# MCU.net
KiCad netlist of a schematic drawn in Altium Designer
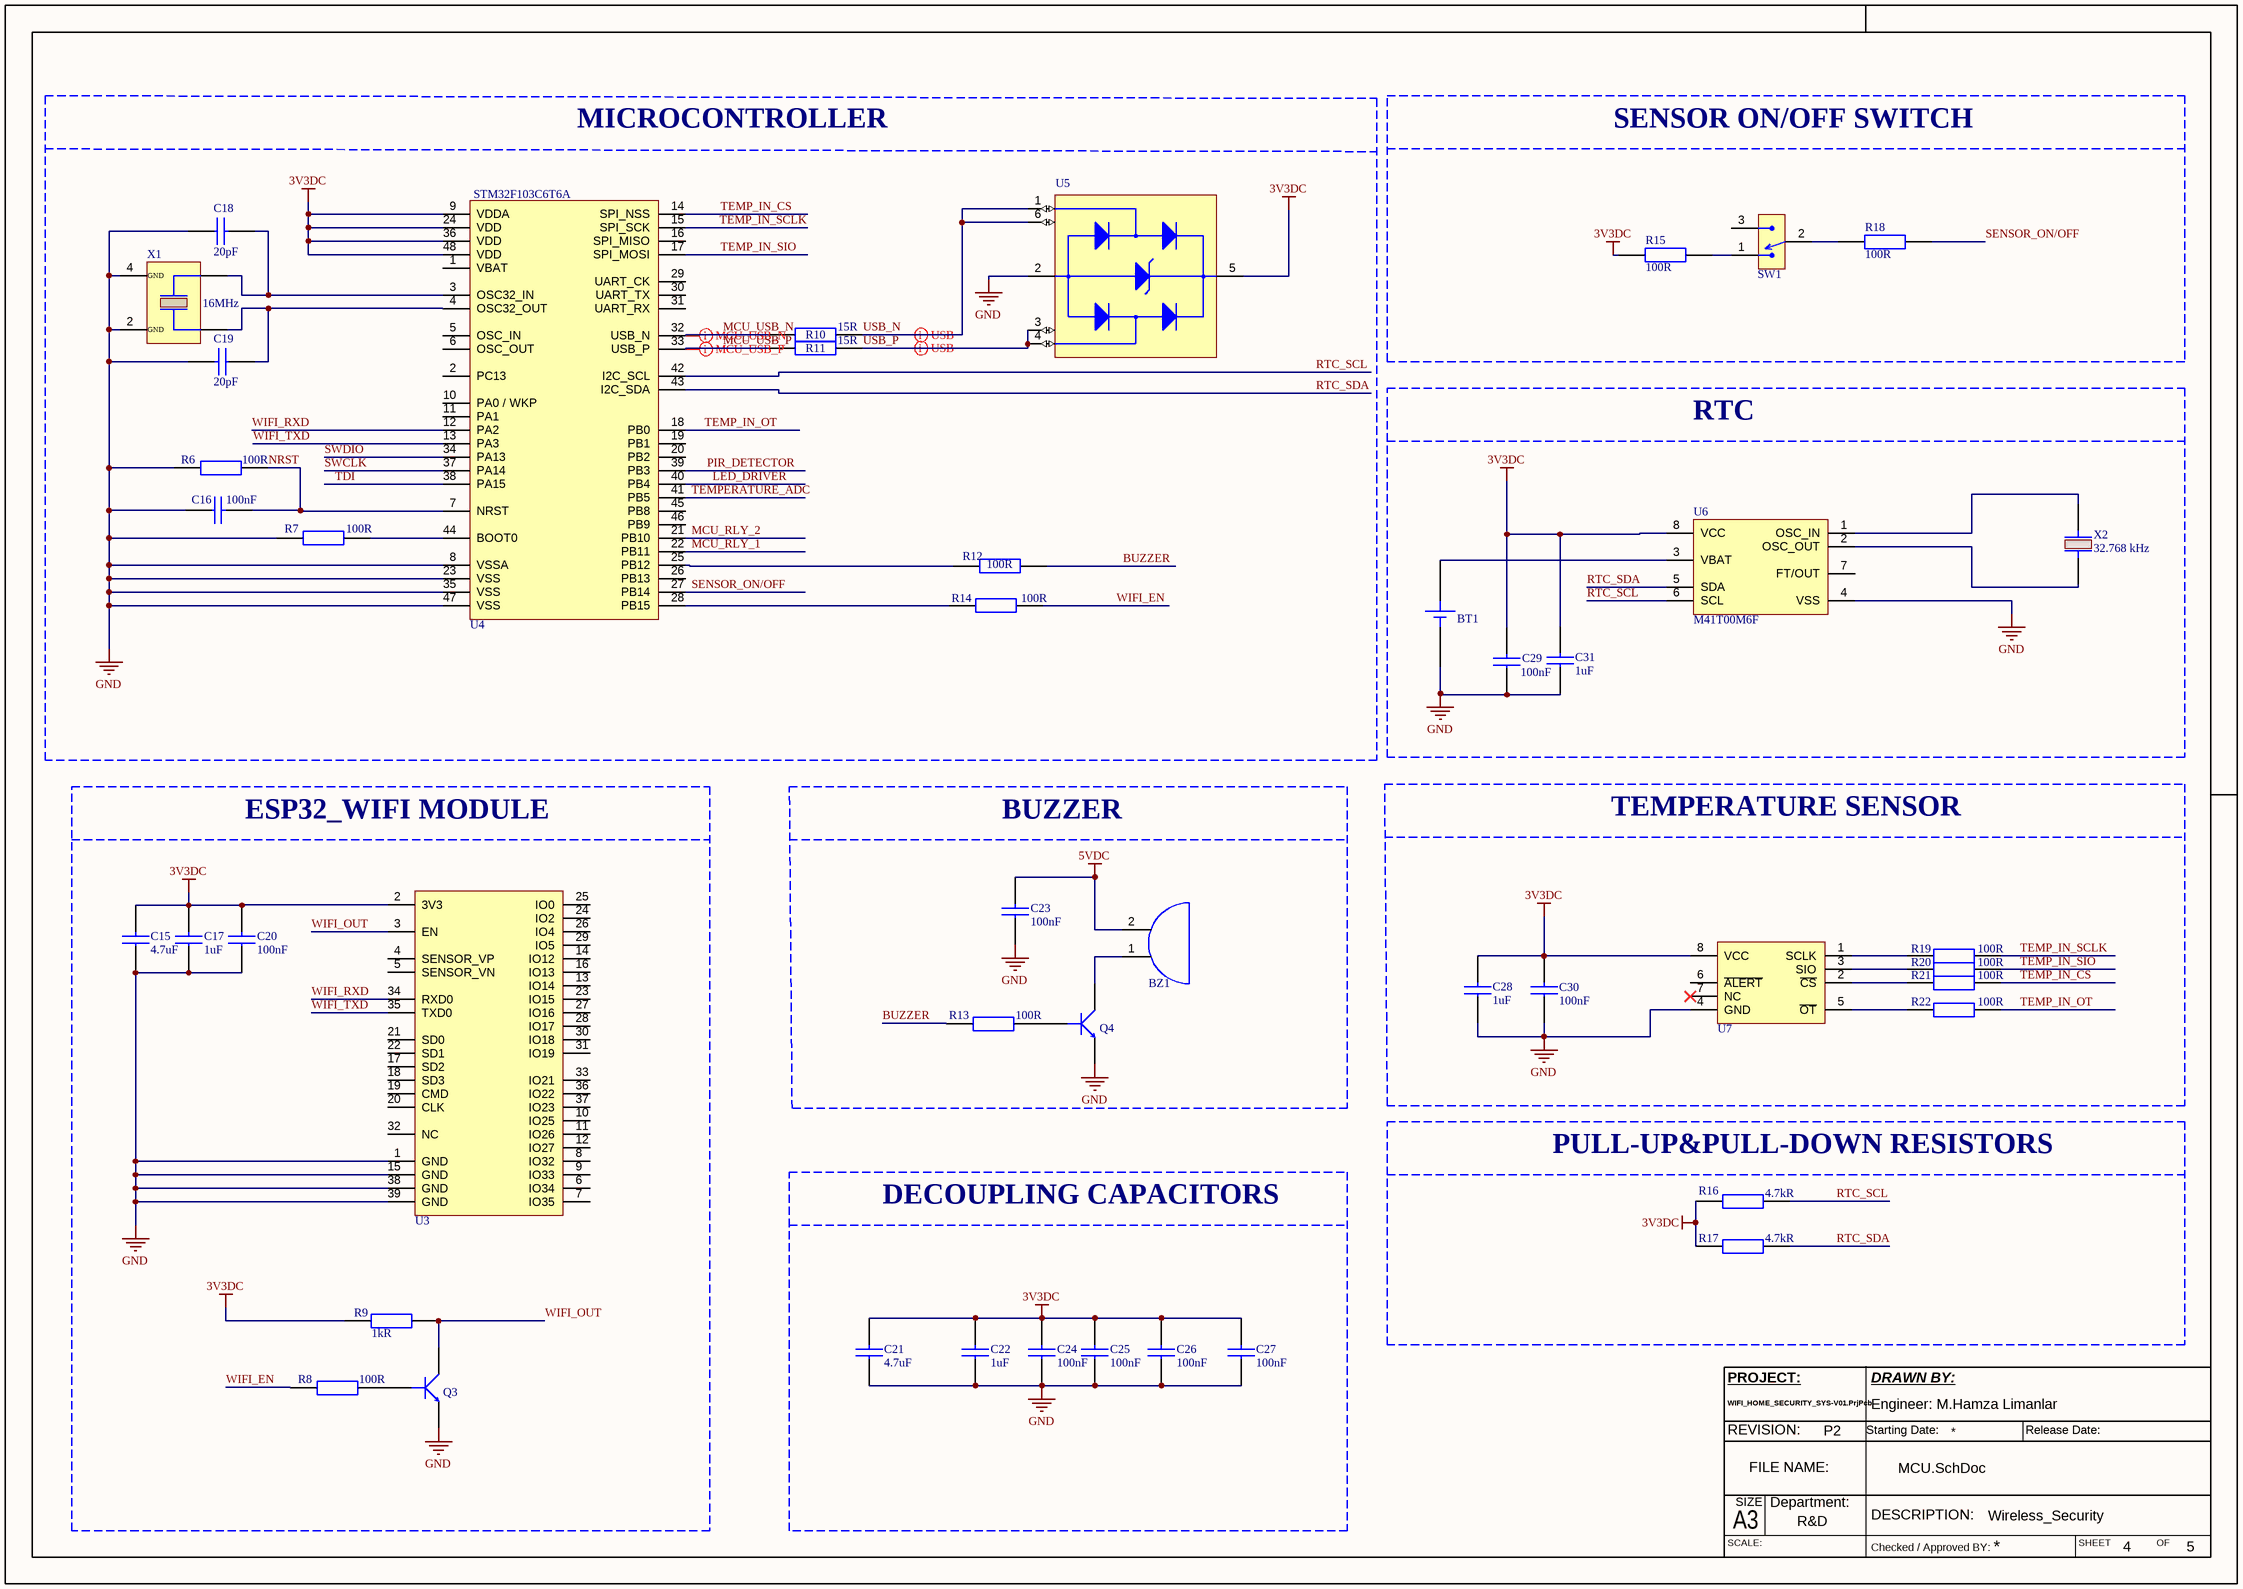
[diagram p0: MCU.SchDoc]

(export (version "E")
  (design (tool "Eeschema 10.0.6"))
  (components
    (comp (ref "BT1")
      (value "FOR CR1220")
      (footprint "1056")
      (description "BATT HOLDER COIN 12.5MM 1CEL SMD")
      (fields
        (field (name "MANUFACTURER") "Adam Equipment")
        (field (name "MANUFACTURER PART NUMBER") "BH-44A-5")
      )
      (libsource (lib "HOME_SECURITY_SYSTEM_PROJECT_SCH_LIBRARY") (part "1056"))
    )
    (comp (ref "BZ1")
      (value "CMI-9605IC-0580T")
      (footprint "CMI-9605IC")
      (description "Buzzers Indicator, Internally Driven Magnetic 5V 30mA 2.7kHz 80dB @ 5V, 10cm Through Hole PC Pins")
      (fields (field (name "MANUFACTURER") "CUI Devices") (field (name "DESIGNED BY") "M.HamzaLimanlar"))
      (libsource (lib "HOME_SECURITY_SYSTEM_PROJECT_LIB") (part "CMI-9605IC-0580T"))
    )
    (comp (ref "C15")
      (value "CL21A475KAQNNNE")
      (footprint "CAP_0805")
      (description "CAP CER 4.7uF %10 0805")
      (fields
        (field (name "MANUFACTURER") "Samsung")
        (field (name "TOLERANCE") "10%")
        (field (name "CAPACITANCE") "4.7uF")
        (field (name "DESIGNED BY") "M.HamzaLimanlar")
      )
      (libsource (lib "HOME_SECURITY_SYSTEM_PROJECT_LIB") (part "CAP CER 4.7uF 0805"))
    )
    (comp (ref "C16")
      (value "C0603C104K5RACTU")
      (footprint "CAP_0603")
      (description "CAP CER 100nF %10 0603 SMD")
      (fields
        (field (name "MANUFACTURER") "KEMET")
        (field (name "TOLERANCE") "10%")
        (field (name "CAPACITANCE") "100nF")
        (field (name "DESIGNED BY") "M.HamzaLimanlar")
      )
      (libsource (lib "HOME_SECURITY_SYSTEM_PROJECT_LIB") (part "CAP CER 100nF 0603"))
    )
    (comp (ref "C17")
      (value "CL21B105KBFNNNE")
      (footprint "CAP_0805")
      (description "CAP CER 1uF %10 0805")
      (fields
        (field (name "MANUFACTURER") "Samsung")
        (field (name "TOLERANCE") "10%")
        (field (name "CAPACITANCE") "1uF")
        (field (name "DESIGNED BY") "M.HamzaLimanlar")
      )
      (libsource (lib "HOME_SECURITY_SYSTEM_PROJECT_LIB") (part "CAP CER 1uF 0805"))
    )
    (comp (ref "C18")
      (value "CL10C200JB8NNNC")
      (footprint "CAP_0603")
      (description "CAP CER 20pF %5 0603 SMD")
      (fields
        (field (name "MANUFACTURER") "Samsung")
        (field (name "TOLERANCE") "5%")
        (field (name "CAPACITANCE") "20pF")
        (field (name "DESIGNED BY") "M.HamzaLimanlar")
      )
      (libsource (lib "HOME_SECURITY_SYSTEM_PROJECT_LIB") (part "CAP CER 20pF 0603"))
    )
    (comp (ref "C19")
      (value "CL10C200JB8NNNC")
      (footprint "CAP_0603")
      (description "CAP CER 20pF %5 0603 SMD")
      (fields
        (field (name "MANUFACTURER") "Samsung")
        (field (name "TOLERANCE") "5%")
        (field (name "CAPACITANCE") "20pF")
        (field (name "DESIGNED BY") "M.HamzaLimanlar")
      )
      (libsource (lib "HOME_SECURITY_SYSTEM_PROJECT_LIB") (part "CAP CER 20pF 0603"))
    )
    (comp (ref "C20")
      (value "CL21B104KBCNNNC")
      (footprint "CAP_0805")
      (description "CAP CER 100nF %10 0805")
      (fields
        (field (name "MANUFACTURER") "Samsung")
        (field (name "TOLERANCE") "10%")
        (field (name "CAPACITANCE") "100nF")
        (field (name "DESIGNED BY") "M.HamzaLimanlar")
      )
      (libsource (lib "HOME_SECURITY_SYSTEM_PROJECT_LIB") (part "CAP CER 100nF 0805"))
    )
    (comp (ref "C21")
      (value "CL21A475KAQNNNE")
      (footprint "CAP_0805")
      (description "CAP CER 4.7uF %10 0805")
      (fields
        (field (name "MANUFACTURER") "Samsung")
        (field (name "TOLERANCE") "10%")
        (field (name "CAPACITANCE") "4.7uF")
        (field (name "DESIGNED BY") "M.HamzaLimanlar")
      )
      (libsource (lib "HOME_SECURITY_SYSTEM_PROJECT_LIB") (part "CAP CER 4.7uF 0805"))
    )
    (comp (ref "C22")
      (value "CL21B105KBFNNNE")
      (footprint "CAP_0805")
      (description "CAP CER 1uF %10 0805")
      (fields
        (field (name "MANUFACTURER") "Samsung")
        (field (name "TOLERANCE") "10%")
        (field (name "CAPACITANCE") "1uF")
        (field (name "DESIGNED BY") "M.HamzaLimanlar")
      )
      (libsource (lib "HOME_SECURITY_SYSTEM_PROJECT_LIB") (part "CAP CER 1uF 0805"))
    )
    (comp (ref "C23")
      (value "CL21B104KBCNNNC")
      (footprint "CAP_0805")
      (description "CAP CER 100nF %10 0805")
      (fields
        (field (name "MANUFACTURER") "Samsung")
        (field (name "TOLERANCE") "10%")
        (field (name "CAPACITANCE") "100nF")
        (field (name "DESIGNED BY") "M.HamzaLimanlar")
      )
      (libsource (lib "HOME_SECURITY_SYSTEM_PROJECT_LIB") (part "CAP CER 100nF 0805"))
    )
    (comp (ref "C24")
      (value "C0603C104K5RACTU")
      (footprint "CAP_0603")
      (description "CAP CER 100nF %10 0603 SMD")
      (fields
        (field (name "MANUFACTURER") "KEMET")
        (field (name "TOLERANCE") "10%")
        (field (name "CAPACITANCE") "100nF")
        (field (name "DESIGNED BY") "M.HamzaLimanlar")
      )
      (libsource (lib "HOME_SECURITY_SYSTEM_PROJECT_LIB") (part "CAP CER 100nF 0603"))
    )
    (comp (ref "C25")
      (value "C0603C104K5RACTU")
      (footprint "CAP_0603")
      (description "CAP CER 100nF %10 0603 SMD")
      (fields
        (field (name "MANUFACTURER") "KEMET")
        (field (name "TOLERANCE") "10%")
        (field (name "CAPACITANCE") "100nF")
        (field (name "DESIGNED BY") "M.HamzaLimanlar")
      )
      (libsource (lib "HOME_SECURITY_SYSTEM_PROJECT_LIB") (part "CAP CER 100nF 0603"))
    )
    (comp (ref "C26")
      (value "C0603C104K5RACTU")
      (footprint "CAP_0603")
      (description "CAP CER 100nF %10 0603 SMD")
      (fields
        (field (name "MANUFACTURER") "KEMET")
        (field (name "TOLERANCE") "10%")
        (field (name "CAPACITANCE") "100nF")
        (field (name "DESIGNED BY") "M.HamzaLimanlar")
      )
      (libsource (lib "HOME_SECURITY_SYSTEM_PROJECT_LIB") (part "CAP CER 100nF 0603"))
    )
    (comp (ref "C27")
      (value "C0603C104K5RACTU")
      (footprint "CAP_0603")
      (description "CAP CER 100nF %10 0603 SMD")
      (fields
        (field (name "MANUFACTURER") "KEMET")
        (field (name "TOLERANCE") "10%")
        (field (name "CAPACITANCE") "100nF")
        (field (name "DESIGNED BY") "M.HamzaLimanlar")
      )
      (libsource (lib "HOME_SECURITY_SYSTEM_PROJECT_LIB") (part "CAP CER 100nF 0603"))
    )
    (comp (ref "C28")
      (value "CL21B105KBFNNNE")
      (footprint "CAP_0805")
      (description "CAP CER 1uF %10 0805")
      (fields
        (field (name "MANUFACTURER") "Samsung")
        (field (name "TOLERANCE") "10%")
        (field (name "CAPACITANCE") "1uF")
        (field (name "DESIGNED BY") "M.HamzaLimanlar")
      )
      (libsource (lib "HOME_SECURITY_SYSTEM_PROJECT_LIB") (part "CAP CER 1uF 0805"))
    )
    (comp (ref "C29")
      (value "CL21B104KBCNNNC")
      (footprint "CAP_0805")
      (description "CAP CER 100nF %10 0805")
      (fields
        (field (name "MANUFACTURER") "Samsung")
        (field (name "TOLERANCE") "10%")
        (field (name "CAPACITANCE") "100nF")
        (field (name "DESIGNED BY") "M.HamzaLimanlar")
      )
      (libsource (lib "HOME_SECURITY_SYSTEM_PROJECT_LIB") (part "CAP CER 100nF 0805"))
    )
    (comp (ref "C30")
      (value "CL21B104KBCNNNC")
      (footprint "CAP_0805")
      (description "CAP CER 100nF %10 0805")
      (fields
        (field (name "MANUFACTURER") "Samsung")
        (field (name "TOLERANCE") "10%")
        (field (name "CAPACITANCE") "100nF")
        (field (name "DESIGNED BY") "M.HamzaLimanlar")
      )
      (libsource (lib "HOME_SECURITY_SYSTEM_PROJECT_LIB") (part "CAP CER 100nF 0805"))
    )
    (comp (ref "C31")
      (value "CL21B105KBFNNNE")
      (footprint "CAP_0805")
      (description "CAP CER 1uF %10 0805")
      (fields
        (field (name "MANUFACTURER") "Samsung")
        (field (name "TOLERANCE") "10%")
        (field (name "CAPACITANCE") "1uF")
        (field (name "DESIGNED BY") "M.HamzaLimanlar")
      )
      (libsource (lib "HOME_SECURITY_SYSTEM_PROJECT_LIB") (part "CAP CER 1uF 0805"))
    )
    (comp (ref "Q3")
      (value "MMBT3904-7-F")
      (footprint "SOT-23F")
      (description "Transistor General Purpose BJT NPN 40 Volt 0.2A Automotive 3-Pin SOT-23")
      (fields (field (name "MANUFACTURER") "Diodes Zetex") (field (name "DESIGNED BY") "M.HamzaLimanlar"))
      (libsource (lib "HOME_SECURITY_SYSTEM_PROJECT_LIB") (part "MMBT3904-7-F"))
    )
    (comp (ref "Q4")
      (value "MMBT3904-7-F")
      (footprint "SOT-23F")
      (description "Transistor General Purpose BJT NPN 40 Volt 0.2A Automotive 3-Pin SOT-23")
      (fields (field (name "MANUFACTURER") "Diodes Zetex") (field (name "DESIGNED BY") "M.HamzaLimanlar"))
      (libsource (lib "HOME_SECURITY_SYSTEM_PROJECT_LIB") (part "MMBT3904-7-F"))
    )
    (comp (ref "R6")
      (value "RC0603JR-07100RL")
      (footprint "RES_0603")
      (description "RES 100 %5 OHM 0603 SMD")
      (fields
        (field (name "MANUFACTURER") "Yageo")
        (field (name "TOLERANCE") "5%")
        (field (name "RESISTANCE") "100R")
        (field (name "DESIGNED BY") "M.HamzaLimanlar")
      )
      (libsource (lib "HOME_SECURITY_SYSTEM_PROJECT_LIB") (part "RES 100 OHM 0603"))
    )
    (comp (ref "R7")
      (value "RC0603JR-07100RL")
      (footprint "RES_0603")
      (description "RES 100 %5 OHM 0603 SMD")
      (fields
        (field (name "MANUFACTURER") "Yageo")
        (field (name "TOLERANCE") "5%")
        (field (name "RESISTANCE") "100R")
        (field (name "DESIGNED BY") "M.HamzaLimanlar")
      )
      (libsource (lib "HOME_SECURITY_SYSTEM_PROJECT_LIB") (part "RES 100 OHM 0603"))
    )
    (comp (ref "R8")
      (value "RC0603JR-07100RL")
      (footprint "RES_0603")
      (description "RES 100 %5 OHM 0603 SMD")
      (fields
        (field (name "MANUFACTURER") "Yageo")
        (field (name "TOLERANCE") "5%")
        (field (name "RESISTANCE") "100R")
        (field (name "DESIGNED BY") "M.HamzaLimanlar")
      )
      (libsource (lib "HOME_SECURITY_SYSTEM_PROJECT_LIB") (part "RES 100 OHM 0603"))
    )
    (comp (ref "R9")
      (value "RC0603FR-0710KL")
      (footprint "RES_0603")
      (description "RES 1K %1 OHM 0603 SMD")
      (fields
        (field (name "MANUFACTURER") "Yageo")
        (field (name "MANUFACTURER PART NUMBER") "RC0603JR-071KL")
        (field (name "RESISTANCE") "1kR")
        (field (name "DESIGNED BY") "M.HamzaLimanlar")
      )
      (libsource (lib "HOME_SECURITY_SYSTEM_PROJECT_LIB") (part "RES 1K OHM 0603"))
    )
    (comp (ref "R10")
      (value "RC0603JR-0715RL")
      (footprint "RES_0603")
      (description "RES 15 %5 OHM 0603 SMD")
      (fields
        (field (name "MANUFACTURER") "Yageo")
        (field (name "TOLERANCE") "5%")
        (field (name "RESISTANCE") "15R")
        (field (name "DESIGNED BY") "M.HamzaLimanlar")
      )
      (libsource (lib "HOME_SECURITY_SYSTEM_PROJECT_LIB") (part "RES 15 OHM 0603"))
    )
    (comp (ref "R11")
      (value "RC0603JR-0715RL")
      (footprint "RES_0603")
      (description "RES 15 %5 OHM 0603 SMD")
      (fields
        (field (name "MANUFACTURER") "Yageo")
        (field (name "TOLERANCE") "5%")
        (field (name "RESISTANCE") "15R")
        (field (name "DESIGNED BY") "M.HamzaLimanlar")
      )
      (libsource (lib "HOME_SECURITY_SYSTEM_PROJECT_LIB") (part "RES 15 OHM 0603"))
    )
    (comp (ref "R12")
      (value "RC0603JR-07100RL")
      (footprint "RES_0603")
      (description "RES 100 %5 OHM 0603 SMD")
      (fields
        (field (name "MANUFACTURER") "Yageo")
        (field (name "TOLERANCE") "5%")
        (field (name "RESISTANCE") "100R")
        (field (name "DESIGNED BY") "M.HamzaLimanlar")
      )
      (libsource (lib "HOME_SECURITY_SYSTEM_PROJECT_LIB") (part "RES 100 OHM 0603"))
    )
    (comp (ref "R13")
      (value "RC0603JR-07100RL")
      (footprint "RES_0603")
      (description "RES 100 %5 OHM 0603 SMD")
      (fields
        (field (name "MANUFACTURER") "Yageo")
        (field (name "TOLERANCE") "5%")
        (field (name "RESISTANCE") "100R")
        (field (name "DESIGNED BY") "M.HamzaLimanlar")
      )
      (libsource (lib "HOME_SECURITY_SYSTEM_PROJECT_LIB") (part "RES 100 OHM 0603"))
    )
    (comp (ref "R14")
      (value "RC0603JR-07100RL")
      (footprint "RES_0603")
      (description "RES 100 %5 OHM 0603 SMD")
      (fields
        (field (name "MANUFACTURER") "Yageo")
        (field (name "TOLERANCE") "5%")
        (field (name "RESISTANCE") "100R")
        (field (name "DESIGNED BY") "M.HamzaLimanlar")
      )
      (libsource (lib "HOME_SECURITY_SYSTEM_PROJECT_LIB") (part "RES 100 OHM 0603"))
    )
    (comp (ref "R15")
      (value "RC0603JR-07100RL")
      (footprint "RES_0603")
      (description "RES 100 %5 OHM 0603 SMD")
      (fields
        (field (name "MANUFACTURER") "Yageo")
        (field (name "TOLERANCE") "5%")
        (field (name "RESISTANCE") "100R")
        (field (name "DESIGNED BY") "M.HamzaLimanlar")
      )
      (libsource (lib "HOME_SECURITY_SYSTEM_PROJECT_LIB") (part "RES 100 OHM 0603"))
    )
    (comp (ref "R16")
      (value "RC0603JR-074K7L")
      (footprint "RES_0603")
      (description "RES 4K7 %5 OHM 0603 SMD")
      (fields
        (field (name "MANUFACTURER") "Yageo")
        (field (name "TOLERANCE") "5%")
        (field (name "RESISTANCE") "4.7kR")
        (field (name "DESIGNED BY") "M.HamzaLimanlar")
      )
      (libsource (lib "HOME_SECURITY_SYSTEM_PROJECT_LIB") (part "RES 4K7 OHM 0603"))
    )
    (comp (ref "R17")
      (value "RC0603JR-074K7L")
      (footprint "RES_0603")
      (description "RES 4K7 %5 OHM 0603 SMD")
      (fields
        (field (name "MANUFACTURER") "Yageo")
        (field (name "TOLERANCE") "5%")
        (field (name "RESISTANCE") "4.7kR")
        (field (name "DESIGNED BY") "M.HamzaLimanlar")
      )
      (libsource (lib "HOME_SECURITY_SYSTEM_PROJECT_LIB") (part "RES 4K7 OHM 0603"))
    )
    (comp (ref "R18")
      (value "RC0603JR-07100RL")
      (footprint "RES_0603")
      (description "RES 100 %5 OHM 0603 SMD")
      (fields
        (field (name "MANUFACTURER") "Yageo")
        (field (name "TOLERANCE") "5%")
        (field (name "RESISTANCE") "100R")
        (field (name "DESIGNED BY") "M.HamzaLimanlar")
      )
      (libsource (lib "HOME_SECURITY_SYSTEM_PROJECT_LIB") (part "RES 100 OHM 0603"))
    )
    (comp (ref "R19")
      (value "RC0603JR-07100RL")
      (footprint "RES_0603")
      (description "RES 100 %5 OHM 0603 SMD")
      (fields
        (field (name "MANUFACTURER") "Yageo")
        (field (name "TOLERANCE") "5%")
        (field (name "RESISTANCE") "100R")
        (field (name "DESIGNED BY") "M.HamzaLimanlar")
      )
      (libsource (lib "HOME_SECURITY_SYSTEM_PROJECT_LIB") (part "RES 100 OHM 0603"))
    )
    (comp (ref "R20")
      (value "RC0603JR-07100RL")
      (footprint "RES_0603")
      (description "RES 100 %5 OHM 0603 SMD")
      (fields
        (field (name "MANUFACTURER") "Yageo")
        (field (name "TOLERANCE") "5%")
        (field (name "RESISTANCE") "100R")
        (field (name "DESIGNED BY") "M.HamzaLimanlar")
      )
      (libsource (lib "HOME_SECURITY_SYSTEM_PROJECT_LIB") (part "RES 100 OHM 0603"))
    )
    (comp (ref "R21")
      (value "RC0603JR-07100RL")
      (footprint "RES_0603")
      (description "RES 100 %5 OHM 0603 SMD")
      (fields
        (field (name "MANUFACTURER") "Yageo")
        (field (name "TOLERANCE") "5%")
        (field (name "RESISTANCE") "100R")
        (field (name "DESIGNED BY") "M.HamzaLimanlar")
      )
      (libsource (lib "HOME_SECURITY_SYSTEM_PROJECT_LIB") (part "RES 100 OHM 0603"))
    )
    (comp (ref "R22")
      (value "RC0603JR-07100RL")
      (footprint "RES_0603")
      (description "RES 100 %5 OHM 0603 SMD")
      (fields
        (field (name "MANUFACTURER") "Yageo")
        (field (name "TOLERANCE") "5%")
        (field (name "RESISTANCE") "100R")
        (field (name "DESIGNED BY") "M.HamzaLimanlar")
      )
      (libsource (lib "HOME_SECURITY_SYSTEM_PROJECT_LIB") (part "RES 100 OHM 0603"))
    )
    (comp (ref "SW1")
      (value "EG1215AA")
      (footprint "EG1215AA")
      (description "Slide Switch, SPDT, 0.025A, 24V, SMD")
      (fields
        (field (name "MANUFACTURER") "E-Switch")
        (field (name "TOLERANCE") "4.95%")
        (field (name "DESIGNED BY") "M.HamzaLimanlar")
      )
      (libsource (lib "HOME_SECURITY_SYSTEM_PROJECT_LIB") (part "EG1215AA"))
    )
    (comp (ref "U3")
      (value "ESP32-WROOM-32")
      (footprint "ESP32-32")
      (description "SMD MODULE, ESP32-D0WDQ6, 32MBIT")
      (fields
        (field (name "MANUFACTURER") "Espressif Systems")
        (field (name "DESIGNED BY") "M.HamzaLimanlar")
      )
      (libsource (lib "HOME_SECURITY_SYSTEM_PROJECT_LIB") (part "ESP32-WROOM-32"))
    )
    (comp (ref "U4")
      (value "STM32F103C6T6A")
      (footprint "LQFP-48")
      (description "MCU 32-bit STM32F ARM Cortex M3 RISC 32KB Flash 2.5V/3.3V 48-Pin LQFP Tray")
      (fields
        (field (name "MANUFACTURER") "STMicroelectronics")
        (field (name "DESIGNED BY") "M.HamzaLimanlar")
      )
      (libsource (lib "HOME_SECURITY_SYSTEM_PROJECT_LIB") (part "STM32F103C6T6A"))
    )
    (comp (ref "U5")
      (value "USBLC6-2SC6")
      (footprint "SOT23-6L")
      (description "TVS DIODE 5.25V 17V SOT23-6")
      (fields
        (field (name "MANUFACTURER") "STMicroelectronics")
        (field (name "DESIGNED BY") "M.HamzaLimanlar")
      )
      (libsource (lib "HOME_SECURITY_SYSTEM_PROJECT_LIB") (part "USB PROTECTION"))
    )
    (comp (ref "U6")
      (value "M41T00M6F")
      (footprint "SOIC8")
      (description "IC RTC CLK/CALENDAR I2C 8-SOIC")
      (fields
        (field (name "MANUFACTURER") "STMicroelectronics")
        (field (name "MANUFACTURER PART NUMBER") "M41T00M6F")
        (field (name "DESIGNED BY") "M.HamzaLimanlar")
      )
      (libsource (lib "HOME_SECURITY_SYSTEM_PROJECT_LIB") (part "M41T00M6F"))
    )
    (comp (ref "U7")
      (value "MAX6662")
      (footprint "SOIC8")
      (description "SENSOR TEMPERATURE SPI 8SOIC")
      (fields
        (field (name "MANUFACTURER") "Maxim")
        (field (name "MANUFACTURER PART NUMBER") "MAX6662MSA+")
        (field (name "DESIGNED BY") "M.HamzaLimanlar")
      )
      (libsource (lib "HOME_SECURITY_SYSTEM_PROJECT_LIB") (part "MAX6662"))
    )
    (comp (ref "X1")
      (value "ECS-160-20-30B-TR")
      (footprint "ECS")
      (description "CRYSTAL 16.0000MHZ 20PF SMD")
      (fields
        (field (name "MANUFACTURER") "ECS International")
        (field (name "TOLERANCE") "50ppm")
        (field (name "FREQUENCY") "16MHz")
        (field (name "DESIGNED BY") "M.HamzaLimanlar")
      )
      (libsource (lib "HOME_SECURITY_SYSTEM_PROJECT_LIB") (part "CRYSTAL 16MHz"))
    )
    (comp (ref "X2")
      (value "ABS05-32.768KHZ-T")
      (footprint "ABS05")
      (description "Crystal, 32.768 kHz, SMD, 1.6mm x 1mm, 12.5 pF, 20 ppm, ABS05 Series")
      (fields
        (field (name "MANUFACTURER") "Abracon")
        (field (name "TOLERANCE") "20ppm")
        (field (name "OPERATING FREQUENCY") "32.768 kHz")
        (field (name "DESIGNED BY") "M.HamzaLimanlar")
      )
      (libsource (lib "HOME_SECURITY_SYSTEM_PROJECT_LIB") (part "CRYSTAL 32768kHZ"))
    )
  )
  (nets
    (net (code "1") (name "/BUZZER") (class "Default")
      (node (ref "R12") (pin "2") (pinfunction "2_2") (pintype "passive"))
      (node (ref "R13") (pin "1") (pinfunction "1_1") (pintype "passive"))
    )
    (net (code "2") (name "/LED_DRIVER") (class "Default")
      (node (ref "U4") (pin "40") (pinfunction "PB4_40") (pintype "passive"))
    )
    (net (code "3") (name "/MCU_RLY_1") (class "Default")
      (node (ref "U4") (pin "22") (pinfunction "PB11_22") (pintype "passive"))
    )
    (net (code "4") (name "/MCU_RLY_2") (class "Default")
      (node (ref "U4") (pin "21") (pinfunction "PB10_21") (pintype "passive"))
    )
    (net (code "5") (name "/MCU_USB_N") (class "Default")
      (node (ref "R10") (pin "1") (pinfunction "1_1") (pintype "passive"))
      (node (ref "U4") (pin "32") (pinfunction "USB_N_32") (pintype "passive"))
    )
    (net (code "6") (name "/MCU_USB_P") (class "Default")
      (node (ref "R11") (pin "1") (pinfunction "1_1") (pintype "passive"))
      (node (ref "U4") (pin "33") (pinfunction "USB_P_33") (pintype "passive"))
    )
    (net (code "7") (name "/NRST") (class "Default")
      (node (ref "C16") (pin "2") (pinfunction "2_2") (pintype "passive"))
      (node (ref "R6") (pin "2") (pinfunction "2_2") (pintype "passive"))
      (node (ref "U4") (pin "7") (pinfunction "NRST_7") (pintype "passive"))
    )
    (net (code "8") (name "/PIR_DETECTOR") (class "Default")
      (node (ref "U4") (pin "39") (pinfunction "PB3_39") (pintype "passive"))
    )
    (net (code "9") (name "/RTC_SCL") (class "Default")
      (node (ref "R16") (pin "2") (pinfunction "2_2") (pintype "passive"))
      (node (ref "U4") (pin "42") (pinfunction "I2C_SCL_42") (pintype "passive"))
      (node (ref "U6") (pin "6") (pinfunction "SCL_6") (pintype "passive"))
    )
    (net (code "10") (name "/RTC_SDA") (class "Default")
      (node (ref "R17") (pin "2") (pinfunction "2_2") (pintype "passive"))
      (node (ref "U4") (pin "43") (pinfunction "I2C_SDA_43") (pintype "passive"))
      (node (ref "U6") (pin "5") (pinfunction "SDA_5") (pintype "passive"))
    )
    (net (code "11") (name "/SENSOR_ON{slash}OFF") (class "Default")
      (node (ref "R18") (pin "2") (pinfunction "2_2") (pintype "passive"))
      (node (ref "U4") (pin "27") (pinfunction "PB14_27") (pintype "passive"))
    )
    (net (code "12") (name "/SWCLK") (class "Default")
      (node (ref "U4") (pin "37") (pinfunction "PA14_37") (pintype "passive"))
    )
    (net (code "13") (name "/SWDIO") (class "Default")
      (node (ref "U4") (pin "34") (pinfunction "PA13_34") (pintype "passive"))
    )
    (net (code "14") (name "/TDI") (class "Default")
      (node (ref "U4") (pin "38") (pinfunction "PA15_38") (pintype "passive"))
    )
    (net (code "15") (name "/TEMPERATURE_ADC") (class "Default")
      (node (ref "U4") (pin "41") (pinfunction "PB5_41") (pintype "passive"))
    )
    (net (code "16") (name "/TEMP_IN_CS") (class "Default")
      (node (ref "R21") (pin "2") (pinfunction "2_2") (pintype "passive"))
      (node (ref "U4") (pin "14") (pinfunction "SPI_NSS_14") (pintype "passive"))
    )
    (net (code "17") (name "/TEMP_IN_OT") (class "Default")
      (node (ref "R22") (pin "2") (pinfunction "2_2") (pintype "passive"))
      (node (ref "U4") (pin "18") (pinfunction "PB0_18") (pintype "passive"))
    )
    (net (code "18") (name "/TEMP_IN_SCLK") (class "Default")
      (node (ref "R19") (pin "2") (pinfunction "2_2") (pintype "passive"))
      (node (ref "U4") (pin "15") (pinfunction "SPI_SCK_15") (pintype "passive"))
    )
    (net (code "19") (name "/TEMP_IN_SIO") (class "Default")
      (node (ref "R20") (pin "2") (pinfunction "2_2") (pintype "passive"))
      (node (ref "U4") (pin "17") (pinfunction "SPI_MOSI_17") (pintype "passive"))
    )
    (net (code "20") (name "/USB_N") (class "Default")
      (node (ref "R10") (pin "2") (pinfunction "2_2") (pintype "passive"))
      (node (ref "U5") (pin "1") (pinfunction "I/O1_1") (pintype "bidirectional"))
      (node (ref "U5") (pin "6") (pinfunction "I/O1_6") (pintype "bidirectional"))
    )
    (net (code "21") (name "/USB_P") (class "Default")
      (node (ref "R11") (pin "2") (pinfunction "2_2") (pintype "passive"))
      (node (ref "U5") (pin "3") (pinfunction "I/O2_3") (pintype "bidirectional"))
      (node (ref "U5") (pin "4") (pinfunction "I/O2_4") (pintype "bidirectional"))
    )
    (net (code "22") (name "/WIFI_EN") (class "Default")
      (node (ref "R14") (pin "2") (pinfunction "2_2") (pintype "passive"))
      (node (ref "R8") (pin "1") (pinfunction "1_1") (pintype "passive"))
    )
    (net (code "23") (name "/WIFI_OUT") (class "Default")
      (node (ref "Q3") (pin "3") (pinfunction "C_3") (pintype "power_in"))
      (node (ref "R9") (pin "2") (pinfunction "2_2") (pintype "passive"))
      (node (ref "U3") (pin "3") (pinfunction "EN_3") (pintype "passive"))
    )
    (net (code "24") (name "/WIFI_RXD") (class "Default")
      (node (ref "U3") (pin "34") (pinfunction "RXD0_34") (pintype "passive"))
      (node (ref "U4") (pin "12") (pinfunction "PA2_12") (pintype "passive"))
    )
    (net (code "25") (name "/WIFI_TXD") (class "Default")
      (node (ref "U3") (pin "35") (pinfunction "TXD0_35") (pintype "passive"))
      (node (ref "U4") (pin "13") (pinfunction "PA3_13") (pintype "passive"))
    )
    (net (code "26") (name "3V3DC") (class "Default")
      (node (ref "C15") (pin "2") (pinfunction "2_2") (pintype "passive"))
      (node (ref "C17") (pin "2") (pinfunction "2_2") (pintype "passive"))
      (node (ref "C20") (pin "2") (pinfunction "2_2") (pintype "passive"))
      (node (ref "C21") (pin "2") (pinfunction "2_2") (pintype "passive"))
      (node (ref "C22") (pin "2") (pinfunction "2_2") (pintype "passive"))
      (node (ref "C24") (pin "2") (pinfunction "2_2") (pintype "passive"))
      (node (ref "C25") (pin "2") (pinfunction "2_2") (pintype "passive"))
      (node (ref "C26") (pin "2") (pinfunction "2_2") (pintype "passive"))
      (node (ref "C27") (pin "2") (pinfunction "2_2") (pintype "passive"))
      (node (ref "C28") (pin "2") (pinfunction "2_2") (pintype "passive"))
      (node (ref "C29") (pin "2") (pinfunction "2_2") (pintype "passive"))
      (node (ref "C30") (pin "2") (pinfunction "2_2") (pintype "passive"))
      (node (ref "C31") (pin "2") (pinfunction "2_2") (pintype "passive"))
      (node (ref "R15") (pin "1") (pinfunction "1_1") (pintype "passive"))
      (node (ref "R16") (pin "1") (pinfunction "1_1") (pintype "passive"))
      (node (ref "R17") (pin "1") (pinfunction "1_1") (pintype "passive"))
      (node (ref "R9") (pin "1") (pinfunction "1_1") (pintype "passive"))
      (node (ref "U3") (pin "2") (pinfunction "3V3_2") (pintype "passive"))
      (node (ref "U4") (pin "24") (pinfunction "VDD_24") (pintype "passive"))
      (node (ref "U4") (pin "36") (pinfunction "VDD_36") (pintype "passive"))
      (node (ref "U4") (pin "48") (pinfunction "VDD_48") (pintype "passive"))
      (node (ref "U4") (pin "9") (pinfunction "VDDA_9") (pintype "passive"))
      (node (ref "U5") (pin "5") (pinfunction "VBUS_5") (pintype "power_in"))
      (node (ref "U6") (pin "8") (pinfunction "VCC_8") (pintype "passive"))
      (node (ref "U7") (pin "8") (pinfunction "VCC_8") (pintype "passive"))
    )
    (net (code "27") (name "5VDC") (class "Default")
      (node (ref "BZ1") (pin "2") (pinfunction "2_2") (pintype "passive"))
      (node (ref "C23") (pin "2") (pinfunction "2_2") (pintype "passive"))
    )
    (net (code "28") (name "GND") (class "Default")
      (node (ref "BT1") (pin "2") (pinfunction "2_2") (pintype "passive"))
      (node (ref "C15") (pin "1") (pinfunction "1_1") (pintype "passive"))
      (node (ref "C16") (pin "1") (pinfunction "1_1") (pintype "passive"))
      (node (ref "C17") (pin "1") (pinfunction "1_1") (pintype "passive"))
      (node (ref "C18") (pin "1") (pinfunction "1_1") (pintype "passive"))
      (node (ref "C19") (pin "2") (pinfunction "2_2") (pintype "passive"))
      (node (ref "C20") (pin "1") (pinfunction "1_1") (pintype "passive"))
      (node (ref "C21") (pin "1") (pinfunction "1_1") (pintype "passive"))
      (node (ref "C22") (pin "1") (pinfunction "1_1") (pintype "passive"))
      (node (ref "C23") (pin "1") (pinfunction "1_1") (pintype "passive"))
      (node (ref "C24") (pin "1") (pinfunction "1_1") (pintype "passive"))
      (node (ref "C25") (pin "1") (pinfunction "1_1") (pintype "passive"))
      (node (ref "C26") (pin "1") (pinfunction "1_1") (pintype "passive"))
      (node (ref "C27") (pin "1") (pinfunction "1_1") (pintype "passive"))
      (node (ref "C28") (pin "1") (pinfunction "1_1") (pintype "passive"))
      (node (ref "C29") (pin "1") (pinfunction "1_1") (pintype "passive"))
      (node (ref "C30") (pin "1") (pinfunction "1_1") (pintype "passive"))
      (node (ref "C31") (pin "1") (pinfunction "1_1") (pintype "passive"))
      (node (ref "Q3") (pin "2") (pinfunction "E_2") (pintype "power_in"))
      (node (ref "Q4") (pin "2") (pinfunction "E_2") (pintype "power_in"))
      (node (ref "R6") (pin "1") (pinfunction "1_1") (pintype "passive"))
      (node (ref "R7") (pin "1") (pinfunction "1_1") (pintype "passive"))
      (node (ref "U3") (pin "1") (pinfunction "GND_1") (pintype "passive"))
      (node (ref "U3") (pin "15") (pinfunction "GND_15") (pintype "passive"))
      (node (ref "U3") (pin "38") (pinfunction "GND_38") (pintype "passive"))
      (node (ref "U3") (pin "39") (pinfunction "GND_39") (pintype "passive"))
      (node (ref "U4") (pin "23") (pinfunction "VSS_23") (pintype "passive"))
      (node (ref "U4") (pin "35") (pinfunction "VSS_35") (pintype "passive"))
      (node (ref "U4") (pin "47") (pinfunction "VSS_47") (pintype "passive"))
      (node (ref "U4") (pin "8") (pinfunction "VSSA_8") (pintype "passive"))
      (node (ref "U5") (pin "2") (pinfunction "GND_2") (pintype "power_in"))
      (node (ref "U6") (pin "4") (pinfunction "VSS_4") (pintype "passive"))
      (node (ref "U7") (pin "4") (pinfunction "GND_4") (pintype "passive"))
      (node (ref "X1") (pin "2") (pinfunction "GND_2") (pintype "passive"))
      (node (ref "X1") (pin "4") (pinfunction "GND_4") (pintype "passive"))
    )
    (net (code "29") (name "Net-(Q3-B)") (class "Default")
      (node (ref "Q3") (pin "1") (pinfunction "B_1") (pintype "power_in"))
      (node (ref "R8") (pin "2") (pinfunction "2_2") (pintype "passive"))
    )
    (net (code "30") (name "Net-(Q4-B)") (class "Default")
      (node (ref "Q4") (pin "1") (pinfunction "B_1") (pintype "power_in"))
      (node (ref "R13") (pin "2") (pinfunction "2_2") (pintype "passive"))
    )
    (net (code "31") (name "Net-(Q4-C)") (class "Default")
      (node (ref "BZ1") (pin "1") (pinfunction "1_1") (pintype "passive"))
      (node (ref "Q4") (pin "3") (pinfunction "C_3") (pintype "power_in"))
    )
    (net (code "32") (name "Net-(R15-Pad2)") (class "Default")
      (node (ref "R15") (pin "2") (pinfunction "2_2") (pintype "passive"))
      (node (ref "SW1") (pin "1") (pinfunction "1_1") (pintype "passive"))
    )
    (net (code "33") (name "Net-(R18-Pad1)") (class "Default")
      (node (ref "R18") (pin "1") (pinfunction "1_1") (pintype "passive"))
      (node (ref "SW1") (pin "2") (pinfunction "2_2") (pintype "passive"))
    )
    (net (code "34") (name "Net-(U4-BOOT0)") (class "Default")
      (node (ref "R7") (pin "2") (pinfunction "2_2") (pintype "passive"))
      (node (ref "U4") (pin "44") (pinfunction "BOOT0_44") (pintype "passive"))
    )
    (net (code "35") (name "Net-(U4-OSC32_IN)") (class "Default")
      (node (ref "C18") (pin "2") (pinfunction "2_2") (pintype "passive"))
      (node (ref "U4") (pin "3") (pinfunction "OSC32_IN_3") (pintype "passive"))
      (node (ref "X1") (pin "3") (pinfunction "3_3") (pintype "passive"))
    )
    (net (code "36") (name "Net-(U4-OSC32_OUT)") (class "Default")
      (node (ref "C19") (pin "1") (pinfunction "1_1") (pintype "passive"))
      (node (ref "U4") (pin "4") (pinfunction "OSC32_OUT_4") (pintype "passive"))
      (node (ref "X1") (pin "1") (pinfunction "1_1") (pintype "passive"))
    )
    (net (code "37") (name "Net-(U4-PB12)") (class "Default")
      (node (ref "R12") (pin "1") (pinfunction "1_1") (pintype "passive"))
      (node (ref "U4") (pin "25") (pinfunction "PB12_25") (pintype "passive"))
    )
    (net (code "38") (name "Net-(U4-PB15)") (class "Default")
      (node (ref "R14") (pin "1") (pinfunction "1_1") (pintype "passive"))
      (node (ref "U4") (pin "28") (pinfunction "PB15_28") (pintype "passive"))
    )
    (net (code "39") (name "Net-(U6-OSC_IN)") (class "Default")
      (node (ref "U6") (pin "1") (pinfunction "OSC_IN_1") (pintype "passive"))
      (node (ref "X2") (pin "2") (pinfunction "2_2") (pintype "passive"))
    )
    (net (code "40") (name "Net-(U6-OSC_OUT)") (class "Default")
      (node (ref "U6") (pin "2") (pinfunction "OSC_OUT_2") (pintype "passive"))
      (node (ref "X2") (pin "1") (pinfunction "1_1") (pintype "passive"))
    )
    (net (code "41") (name "Net-(U6-VBAT)") (class "Default")
      (node (ref "BT1") (pin "1") (pinfunction "1_1") (pintype "passive"))
      (node (ref "U6") (pin "3") (pinfunction "VBAT_3") (pintype "passive"))
    )
    (net (code "42") (name "Net-(U7-SCLK)") (class "Default")
      (node (ref "R19") (pin "1") (pinfunction "1_1") (pintype "passive"))
      (node (ref "U7") (pin "1") (pinfunction "SCLK_1") (pintype "passive"))
    )
    (net (code "43") (name "Net-(U7-SIO)") (class "Default")
      (node (ref "R20") (pin "1") (pinfunction "1_1") (pintype "passive"))
      (node (ref "U7") (pin "3") (pinfunction "SIO_3") (pintype "passive"))
    )
    (net (code "44") (name "Net-(U7-~{CS})") (class "Default")
      (node (ref "R21") (pin "1") (pinfunction "1_1") (pintype "passive"))
      (node (ref "U7") (pin "2") (pinfunction "~{CS}_2") (pintype "passive"))
    )
    (net (code "45") (name "Net-(U7-~{OT})") (class "Default")
      (node (ref "R22") (pin "1") (pinfunction "1_1") (pintype "passive"))
      (node (ref "U7") (pin "5") (pinfunction "~{OT}_5") (pintype "passive"))
    )
    (net (code "46") (name "unconnected-(SW1-Pad3)") (class "Default")
      (node (ref "SW1") (pin "3") (pinfunction "3_3") (pintype "passive"))
    )
    (net (code "47") (name "unconnected-(U3-CLK-Pad20)") (class "Default")
      (node (ref "U3") (pin "20") (pinfunction "CLK_20") (pintype "passive"))
    )
    (net (code "48") (name "unconnected-(U3-CMD-Pad19)") (class "Default")
      (node (ref "U3") (pin "19") (pinfunction "CMD_19") (pintype "passive"))
    )
    (net (code "49") (name "unconnected-(U3-IO0-Pad25)") (class "Default")
      (node (ref "U3") (pin "25") (pinfunction "IO0_25") (pintype "passive"))
    )
    (net (code "50") (name "unconnected-(U3-IO2-Pad24)") (class "Default")
      (node (ref "U3") (pin "24") (pinfunction "IO2_24") (pintype "passive"))
    )
    (net (code "51") (name "unconnected-(U3-IO4-Pad26)") (class "Default")
      (node (ref "U3") (pin "26") (pinfunction "IO4_26") (pintype "passive"))
    )
    (net (code "52") (name "unconnected-(U3-IO5-Pad29)") (class "Default")
      (node (ref "U3") (pin "29") (pinfunction "IO5_29") (pintype "passive"))
    )
    (net (code "53") (name "unconnected-(U3-IO12-Pad14)") (class "Default")
      (node (ref "U3") (pin "14") (pinfunction "IO12_14") (pintype "passive"))
    )
    (net (code "54") (name "unconnected-(U3-IO13-Pad16)") (class "Default")
      (node (ref "U3") (pin "16") (pinfunction "IO13_16") (pintype "passive"))
    )
    (net (code "55") (name "unconnected-(U3-IO14-Pad13)") (class "Default")
      (node (ref "U3") (pin "13") (pinfunction "IO14_13") (pintype "passive"))
    )
    (net (code "56") (name "unconnected-(U3-IO15-Pad23)") (class "Default")
      (node (ref "U3") (pin "23") (pinfunction "IO15_23") (pintype "passive"))
    )
    (net (code "57") (name "unconnected-(U3-IO16-Pad27)") (class "Default")
      (node (ref "U3") (pin "27") (pinfunction "IO16_27") (pintype "passive"))
    )
    (net (code "58") (name "unconnected-(U3-IO17-Pad28)") (class "Default")
      (node (ref "U3") (pin "28") (pinfunction "IO17_28") (pintype "passive"))
    )
    (net (code "59") (name "unconnected-(U3-IO18-Pad30)") (class "Default")
      (node (ref "U3") (pin "30") (pinfunction "IO18_30") (pintype "passive"))
    )
    (net (code "60") (name "unconnected-(U3-IO19-Pad31)") (class "Default")
      (node (ref "U3") (pin "31") (pinfunction "IO19_31") (pintype "passive"))
    )
    (net (code "61") (name "unconnected-(U3-IO21-Pad33)") (class "Default")
      (node (ref "U3") (pin "33") (pinfunction "IO21_33") (pintype "passive"))
    )
    (net (code "62") (name "unconnected-(U3-IO22-Pad36)") (class "Default")
      (node (ref "U3") (pin "36") (pinfunction "IO22_36") (pintype "passive"))
    )
    (net (code "63") (name "unconnected-(U3-IO23-Pad37)") (class "Default")
      (node (ref "U3") (pin "37") (pinfunction "IO23_37") (pintype "passive"))
    )
    (net (code "64") (name "unconnected-(U3-IO25-Pad10)") (class "Default")
      (node (ref "U3") (pin "10") (pinfunction "IO25_10") (pintype "passive"))
    )
    (net (code "65") (name "unconnected-(U3-IO26-Pad11)") (class "Default")
      (node (ref "U3") (pin "11") (pinfunction "IO26_11") (pintype "passive"))
    )
    (net (code "66") (name "unconnected-(U3-IO27-Pad12)") (class "Default")
      (node (ref "U3") (pin "12") (pinfunction "IO27_12") (pintype "passive"))
    )
    (net (code "67") (name "unconnected-(U3-IO32-Pad8)") (class "Default")
      (node (ref "U3") (pin "8") (pinfunction "IO32_8") (pintype "passive"))
    )
    (net (code "68") (name "unconnected-(U3-IO33-Pad9)") (class "Default")
      (node (ref "U3") (pin "9") (pinfunction "IO33_9") (pintype "passive"))
    )
    (net (code "69") (name "unconnected-(U3-IO34-Pad6)") (class "Default")
      (node (ref "U3") (pin "6") (pinfunction "IO34_6") (pintype "passive"))
    )
    (net (code "70") (name "unconnected-(U3-IO35-Pad7)") (class "Default")
      (node (ref "U3") (pin "7") (pinfunction "IO35_7") (pintype "passive"))
    )
    (net (code "71") (name "unconnected-(U3-NC-Pad32)") (class "Default")
      (node (ref "U3") (pin "32") (pinfunction "NC_32") (pintype "passive"))
    )
    (net (code "72") (name "unconnected-(U3-SD0-Pad21)") (class "Default")
      (node (ref "U3") (pin "21") (pinfunction "SD0_21") (pintype "passive"))
    )
    (net (code "73") (name "unconnected-(U3-SD1-Pad22)") (class "Default")
      (node (ref "U3") (pin "22") (pinfunction "SD1_22") (pintype "passive"))
    )
    (net (code "74") (name "unconnected-(U3-SD2-Pad17)") (class "Default")
      (node (ref "U3") (pin "17") (pinfunction "SD2_17") (pintype "passive"))
    )
    (net (code "75") (name "unconnected-(U3-SD3-Pad18)") (class "Default")
      (node (ref "U3") (pin "18") (pinfunction "SD3_18") (pintype "passive"))
    )
    (net (code "76") (name "unconnected-(U3-SENSOR_VN-Pad5)") (class "Default")
      (node (ref "U3") (pin "5") (pinfunction "SENSOR_VN_5") (pintype "passive"))
    )
    (net (code "77") (name "unconnected-(U3-SENSOR_VP-Pad4)") (class "Default")
      (node (ref "U3") (pin "4") (pinfunction "SENSOR_VP_4") (pintype "passive"))
    )
    (net (code "78") (name "unconnected-(U4-OSC_IN-Pad5)") (class "Default")
      (node (ref "U4") (pin "5") (pinfunction "OSC_IN_5") (pintype "passive"))
    )
    (net (code "79") (name "unconnected-(U4-OSC_OUT-Pad6)") (class "Default")
      (node (ref "U4") (pin "6") (pinfunction "OSC_OUT_6") (pintype "passive"))
    )
    (net (code "80") (name "unconnected-(U4-PA0_{slash}_WKP-Pad10)") (class "Default")
      (node (ref "U4") (pin "10") (pinfunction "PA0_/_WKP_10") (pintype "passive"))
    )
    (net (code "81") (name "unconnected-(U4-PA1-Pad11)") (class "Default")
      (node (ref "U4") (pin "11") (pinfunction "PA1_11") (pintype "passive"))
    )
    (net (code "82") (name "unconnected-(U4-PB1-Pad19)") (class "Default")
      (node (ref "U4") (pin "19") (pinfunction "PB1_19") (pintype "passive"))
    )
    (net (code "83") (name "unconnected-(U4-PB2-Pad20)") (class "Default")
      (node (ref "U4") (pin "20") (pinfunction "PB2_20") (pintype "passive"))
    )
    (net (code "84") (name "unconnected-(U4-PB8-Pad45)") (class "Default")
      (node (ref "U4") (pin "45") (pinfunction "PB8_45") (pintype "passive"))
    )
    (net (code "85") (name "unconnected-(U4-PB9-Pad46)") (class "Default")
      (node (ref "U4") (pin "46") (pinfunction "PB9_46") (pintype "passive"))
    )
    (net (code "86") (name "unconnected-(U4-PB13-Pad26)") (class "Default")
      (node (ref "U4") (pin "26") (pinfunction "PB13_26") (pintype "passive"))
    )
    (net (code "87") (name "unconnected-(U4-PC13-Pad2)") (class "Default")
      (node (ref "U4") (pin "2") (pinfunction "PC13_2") (pintype "passive"))
    )
    (net (code "88") (name "unconnected-(U4-SPI_MISO-Pad16)") (class "Default")
      (node (ref "U4") (pin "16") (pinfunction "SPI_MISO_16") (pintype "passive"))
    )
    (net (code "89") (name "unconnected-(U4-UART_CK-Pad29)") (class "Default")
      (node (ref "U4") (pin "29") (pinfunction "UART_CK_29") (pintype "passive"))
    )
    (net (code "90") (name "unconnected-(U4-UART_RX-Pad31)") (class "Default")
      (node (ref "U4") (pin "31") (pinfunction "UART_RX_31") (pintype "passive"))
    )
    (net (code "91") (name "unconnected-(U4-UART_TX-Pad30)") (class "Default")
      (node (ref "U4") (pin "30") (pinfunction "UART_TX_30") (pintype "passive"))
    )
    (net (code "92") (name "unconnected-(U4-VBAT-Pad1)") (class "Default")
      (node (ref "U4") (pin "1") (pinfunction "VBAT_1") (pintype "passive"))
    )
    (net (code "93") (name "unconnected-(U6-FT{slash}OUT-Pad7)") (class "Default")
      (node (ref "U6") (pin "7") (pinfunction "FT/OUT_7") (pintype "passive"))
    )
    (net (code "94") (name "unconnected-(U7-NC-Pad7)") (class "Default")
      (node (ref "U7") (pin "7") (pinfunction "NC_7") (pintype "passive+no_connect"))
    )
    (net (code "95") (name "unconnected-(U7-~{ALERT}-Pad6)") (class "Default")
      (node (ref "U7") (pin "6") (pinfunction "~{ALERT}_6") (pintype "passive"))
    )
  )
)
